# hardware-pcb.net
KiCad netlist of a schematic drawn in EAGLE
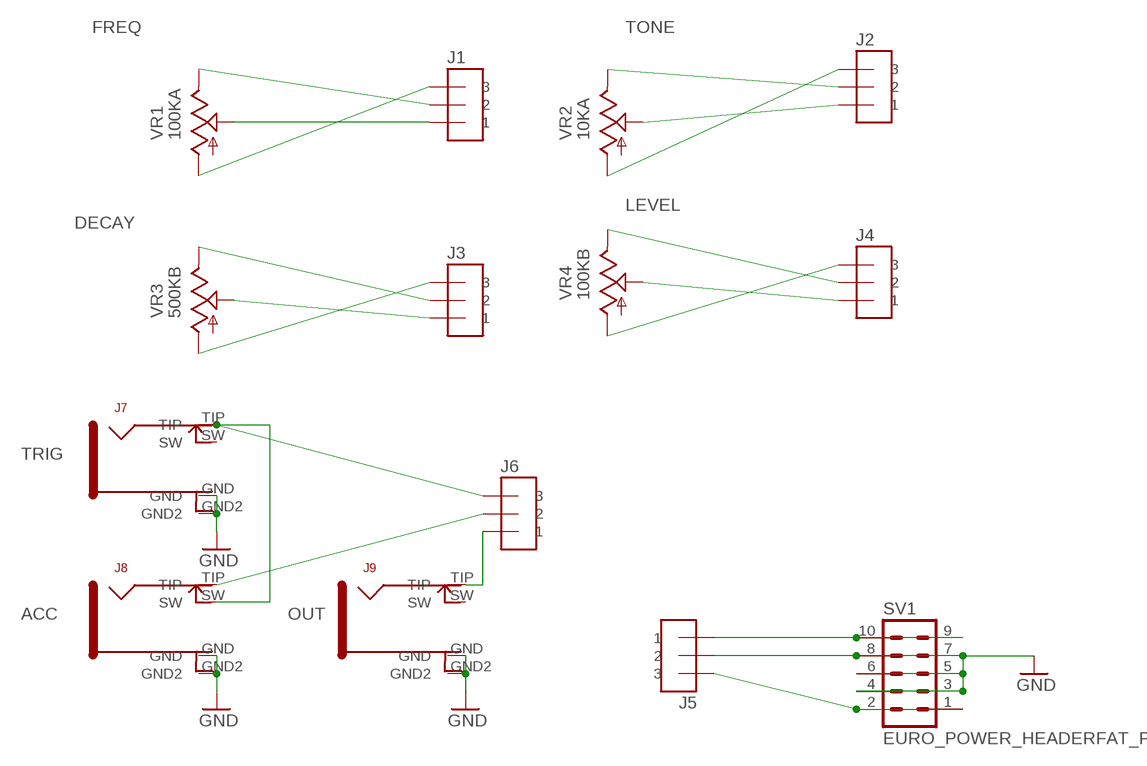
[diagram p0: schematic, sheet 1]

(export (version "E")
  (design (tool "Eeschema 10.0.6"))
  (components
    (comp (ref "J1")
      (value "3X1_2_54_HEADER")
      (footprint "eagle-import:3X1_2_54_HEADER")
      (libsource (lib "eagle-import") (part "3X1_2_54_HEADER"))
    )
    (comp (ref "J2")
      (value "3X1_2_54_HEADER")
      (footprint "eagle-import:3X1_2_54_HEADER")
      (libsource (lib "eagle-import") (part "3X1_2_54_HEADER"))
    )
    (comp (ref "J3")
      (value "3X1_2_54_HEADER")
      (footprint "eagle-import:3X1_2_54_HEADER")
      (libsource (lib "eagle-import") (part "3X1_2_54_HEADER"))
    )
    (comp (ref "J4")
      (value "3X1_2_54_HEADER")
      (footprint "eagle-import:3X1_2_54_HEADER")
      (libsource (lib "eagle-import") (part "3X1_2_54_HEADER"))
    )
    (comp (ref "J5")
      (value "PWR")
      (footprint "eagle-import:3X1_2_54_HEADER")
      (libsource (lib "eagle-import") (part "3X1_2_54_HEADER"))
    )
    (comp (ref "J6")
      (value "3X1_2_54_HEADER")
      (footprint "eagle-import:3X1_2_54_HEADER")
      (libsource (lib "eagle-import") (part "3X1_2_54_HEADER"))
    )
    (comp (ref "J7")
      (value "WQP_PJ_301BM")
      (footprint "eagle-import:WQP_PJ_301BM")
      (libsource (lib "eagle-import") (part "WQP_PJ_301BM"))
    )
    (comp (ref "J8")
      (value "WQP_PJ_301BM")
      (footprint "eagle-import:WQP_PJ_301BM")
      (libsource (lib "eagle-import") (part "WQP_PJ_301BM"))
    )
    (comp (ref "J9")
      (value "WQP_PJ_301BM")
      (footprint "eagle-import:WQP_PJ_301BM")
      (libsource (lib "eagle-import") (part "WQP_PJ_301BM"))
    )
    (comp (ref "SV1")
      (value "EURO_POWER_HEADERFAT_PADS")
      (footprint "eagle-import:EURO_PWR_HEADER_FAT")
      (libsource (lib "eagle-import") (part "EURO_POWER_HEADERFAT_PADS"))
    )
    (comp (ref "VR1")
      (value "100KA")
      (footprint "eagle-import:ALPS_POT_VERTICAL_PS")
      (libsource (lib "eagle-import") (part "ALPSPOT_VERT_9MM"))
    )
    (comp (ref "VR2")
      (value "10KA")
      (footprint "eagle-import:ALPS_POT_VERTICAL_PS")
      (libsource (lib "eagle-import") (part "ALPSPOT_VERT_9MM"))
    )
    (comp (ref "VR3")
      (value "500KB")
      (footprint "eagle-import:ALPS_POT_VERTICAL_PS")
      (libsource (lib "eagle-import") (part "ALPSPOT_VERT_9MM"))
    )
    (comp (ref "VR4")
      (value "100KB")
      (footprint "eagle-import:ALPS_POT_VERTICAL_PS")
      (libsource (lib "eagle-import") (part "ALPSPOT_VERT_9MM"))
    )
  )
  (nets
    (net (code "1") (name "GND") (class "Default")
      (node (ref "J5") (pin "2") (pinfunction "2_2") (pintype "bidirectional"))
      (node (ref "J7") (pin "GND") (pinfunction "GND_GND") (pintype "passive"))
      (node (ref "J7") (pin "GND2") (pinfunction "GND2_GND2") (pintype "passive"))
      (node (ref "J8") (pin "GND") (pinfunction "GND_GND") (pintype "passive"))
      (node (ref "J8") (pin "GND2") (pinfunction "GND2_GND2") (pintype "passive"))
      (node (ref "J9") (pin "GND") (pinfunction "GND_GND") (pintype "passive"))
      (node (ref "J9") (pin "GND2") (pinfunction "GND2_GND2") (pintype "passive"))
      (node (ref "SV1") (pin "3") (pinfunction "3_3") (pintype "passive"))
      (node (ref "SV1") (pin "4") (pinfunction "4_4") (pintype "passive"))
      (node (ref "SV1") (pin "5") (pinfunction "5_5") (pintype "passive"))
      (node (ref "SV1") (pin "6") (pinfunction "6_6") (pintype "passive"))
      (node (ref "SV1") (pin "7") (pinfunction "7_7") (pintype "passive"))
      (node (ref "SV1") (pin "8") (pinfunction "8_8") (pintype "passive"))
    )
    (net (code "2") (name "Net-(J5-Pad1)") (class "Default")
      (node (ref "J5") (pin "1") (pinfunction "1_1") (pintype "bidirectional"))
      (node (ref "SV1") (pin "10") (pinfunction "10_10") (pintype "passive"))
      (node (ref "SV1") (pin "9") (pinfunction "9_9") (pintype "passive"))
    )
    (net (code "3") (name "Net-(J5-Pad3)") (class "Default")
      (node (ref "J5") (pin "3") (pinfunction "3_3") (pintype "bidirectional"))
      (node (ref "SV1") (pin "1") (pinfunction "1_1") (pintype "passive"))
      (node (ref "SV1") (pin "2") (pinfunction "2_2") (pintype "passive"))
    )
    (net (code "4") (name "Net-(J6-Pad1)") (class "Default")
      (node (ref "J6") (pin "1") (pinfunction "1_1") (pintype "bidirectional"))
      (node (ref "J9") (pin "TIP") (pinfunction "TIP_TIP") (pintype "passive"))
    )
    (net (code "5") (name "Net-(J6-Pad2)") (class "Default")
      (node (ref "J6") (pin "2") (pinfunction "2_2") (pintype "bidirectional"))
      (node (ref "J8") (pin "TIP") (pinfunction "TIP_TIP") (pintype "passive"))
    )
    (net (code "6") (name "Net-(J6-Pad3)") (class "Default")
      (node (ref "J6") (pin "3") (pinfunction "3_3") (pintype "bidirectional"))
      (node (ref "J7") (pin "TIP") (pinfunction "TIP_TIP") (pintype "passive"))
      (node (ref "J8") (pin "SW") (pinfunction "SW_SW") (pintype "passive"))
    )
    (net (code "7") (name "Net-(VR1-A)") (class "Default")
      (node (ref "J1") (pin "3") (pinfunction "3_3") (pintype "bidirectional"))
      (node (ref "VR1") (pin "P$1") (pinfunction "A_P$1") (pintype "passive"))
    )
    (net (code "8") (name "Net-(VR1-E)") (class "Default")
      (node (ref "J1") (pin "2") (pinfunction "2_2") (pintype "bidirectional"))
      (node (ref "VR1") (pin "P$2") (pinfunction "E_P$2") (pintype "passive"))
    )
    (net (code "9") (name "Net-(VR1-S)") (class "Default")
      (node (ref "J1") (pin "1") (pinfunction "1_1") (pintype "bidirectional"))
      (node (ref "VR1") (pin "P$3") (pinfunction "S_P$3") (pintype "passive"))
    )
    (net (code "10") (name "Net-(VR2-A)") (class "Default")
      (node (ref "J2") (pin "3") (pinfunction "3_3") (pintype "bidirectional"))
      (node (ref "VR2") (pin "P$1") (pinfunction "A_P$1") (pintype "passive"))
    )
    (net (code "11") (name "Net-(VR2-E)") (class "Default")
      (node (ref "J2") (pin "2") (pinfunction "2_2") (pintype "bidirectional"))
      (node (ref "VR2") (pin "P$2") (pinfunction "E_P$2") (pintype "passive"))
    )
    (net (code "12") (name "Net-(VR2-S)") (class "Default")
      (node (ref "J2") (pin "1") (pinfunction "1_1") (pintype "bidirectional"))
      (node (ref "VR2") (pin "P$3") (pinfunction "S_P$3") (pintype "passive"))
    )
    (net (code "13") (name "Net-(VR3-A)") (class "Default")
      (node (ref "J3") (pin "3") (pinfunction "3_3") (pintype "bidirectional"))
      (node (ref "VR3") (pin "P$1") (pinfunction "A_P$1") (pintype "passive"))
    )
    (net (code "14") (name "Net-(VR3-E)") (class "Default")
      (node (ref "J3") (pin "2") (pinfunction "2_2") (pintype "bidirectional"))
      (node (ref "VR3") (pin "P$2") (pinfunction "E_P$2") (pintype "passive"))
    )
    (net (code "15") (name "Net-(VR3-S)") (class "Default")
      (node (ref "J3") (pin "1") (pinfunction "1_1") (pintype "bidirectional"))
      (node (ref "VR3") (pin "P$3") (pinfunction "S_P$3") (pintype "passive"))
    )
    (net (code "16") (name "Net-(VR4-A)") (class "Default")
      (node (ref "J4") (pin "3") (pinfunction "3_3") (pintype "bidirectional"))
      (node (ref "VR4") (pin "P$1") (pinfunction "A_P$1") (pintype "passive"))
    )
    (net (code "17") (name "Net-(VR4-E)") (class "Default")
      (node (ref "J4") (pin "2") (pinfunction "2_2") (pintype "bidirectional"))
      (node (ref "VR4") (pin "P$2") (pinfunction "E_P$2") (pintype "passive"))
    )
    (net (code "18") (name "Net-(VR4-S)") (class "Default")
      (node (ref "J4") (pin "1") (pinfunction "1_1") (pintype "bidirectional"))
      (node (ref "VR4") (pin "P$3") (pinfunction "S_P$3") (pintype "passive"))
    )
    (net (code "19") (name "unconnected-(J7-PadSW)") (class "Default")
      (node (ref "J7") (pin "SW") (pinfunction "SW_SW") (pintype "passive"))
    )
    (net (code "20") (name "unconnected-(J9-PadSW)") (class "Default")
      (node (ref "J9") (pin "SW") (pinfunction "SW_SW") (pintype "passive"))
    )
  )
)
